# locker_unit.net
KiCad netlist of a schematic drawn in EAGLE
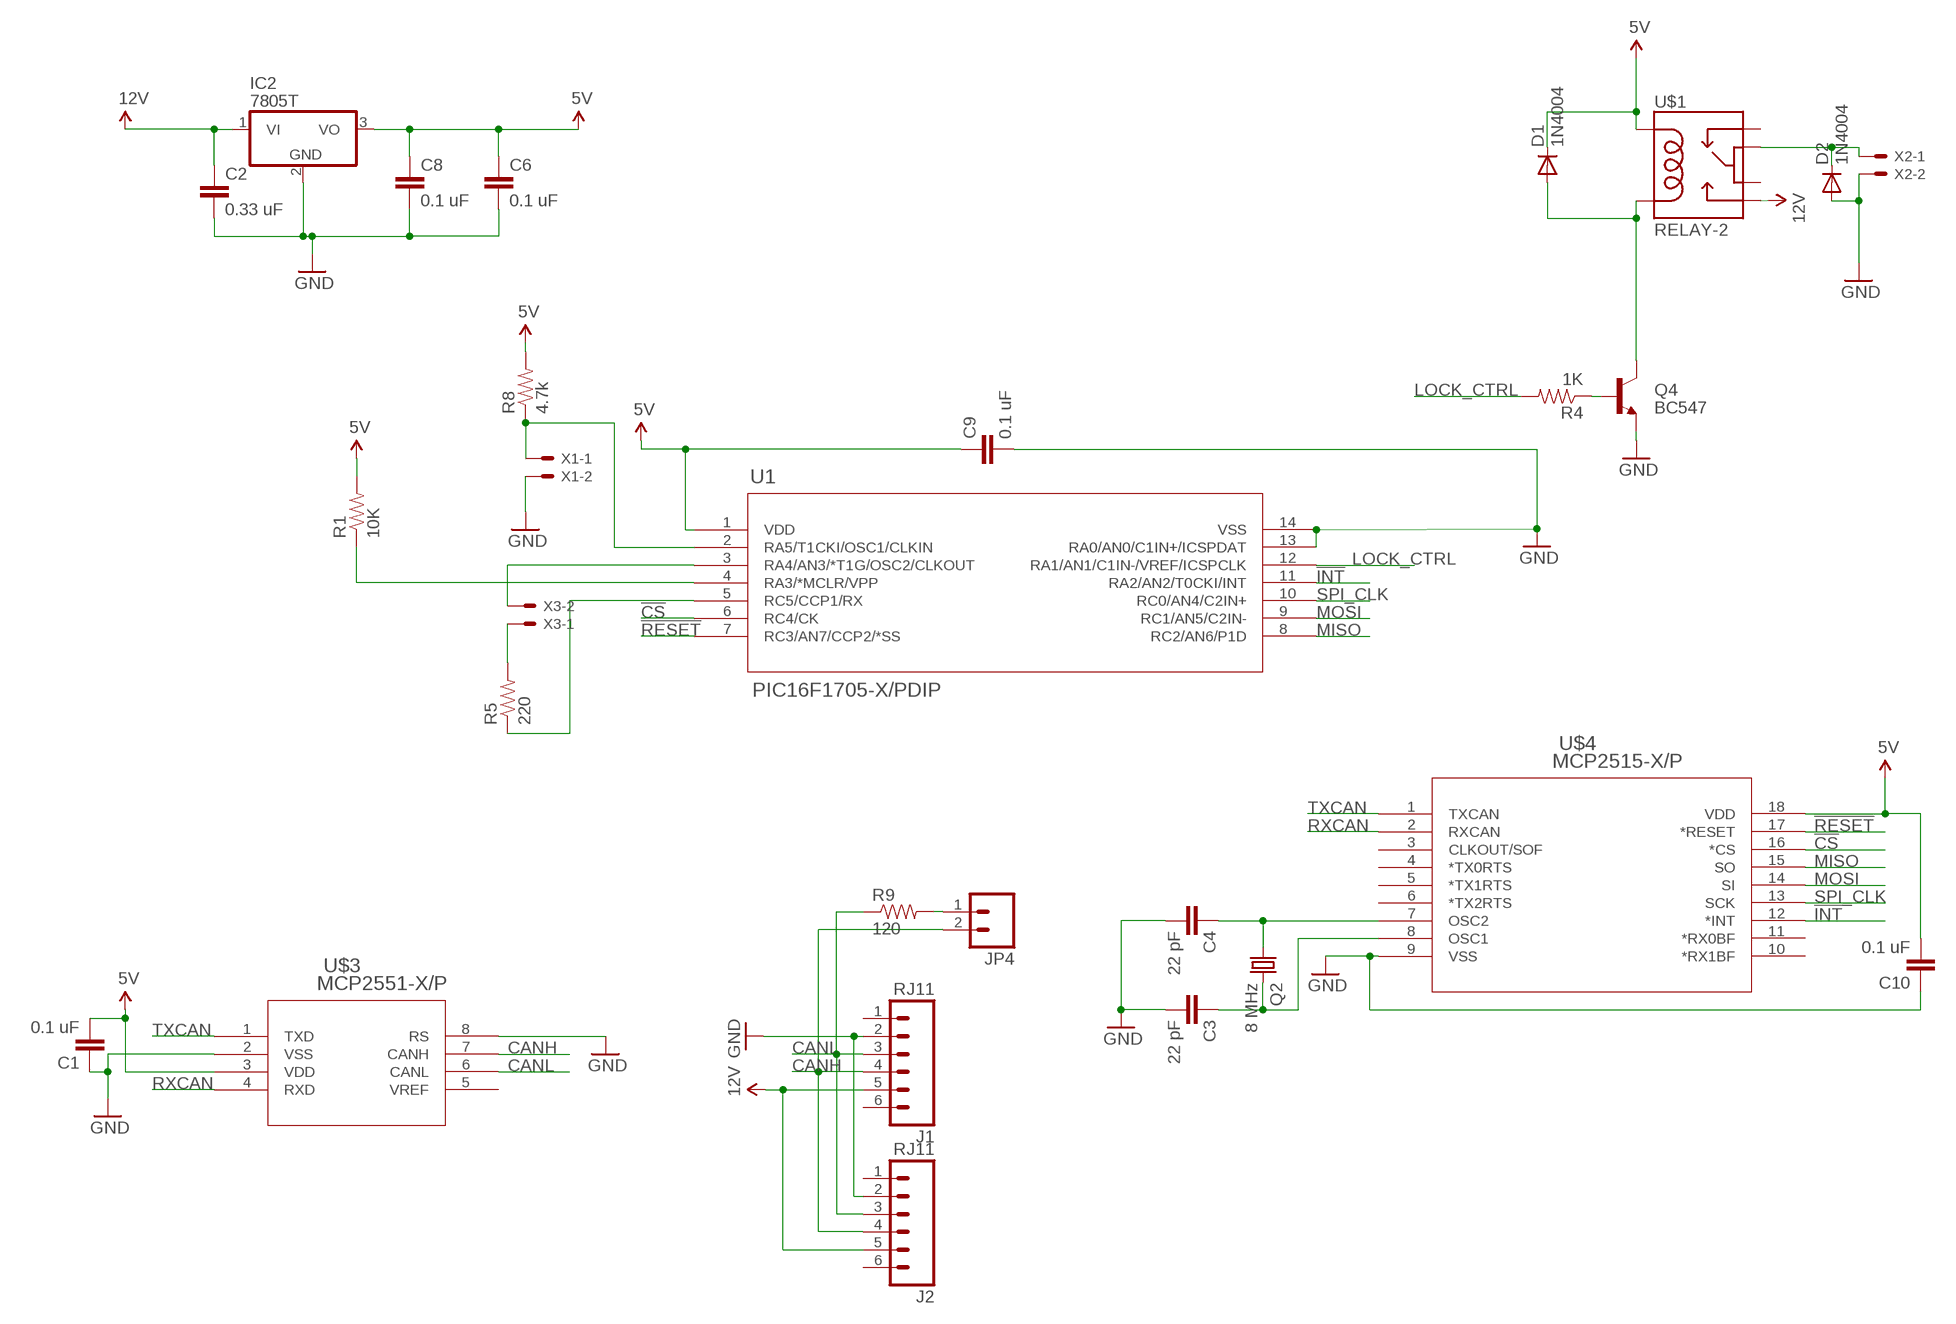
[diagram p0: schematic, sheet 1]

(export (version "E")
  (design (tool "Eeschema 10.0.6"))
  (components
    (comp (ref "C1")
      (value "0.1 uF")
      (footprint "eagle-import:C050-030X075")
      (libsource (lib "eagle-import") (part "C-EU050-030X075"))
    )
    (comp (ref "C2")
      (value "0.33 uF")
      (footprint "eagle-import:C050-030X075")
      (libsource (lib "eagle-import") (part "C-EU050-030X075"))
    )
    (comp (ref "C3")
      (value "22 pF")
      (footprint "eagle-import:C025-025X050")
      (libsource (lib "eagle-import") (part "C-EU025-025X050"))
    )
    (comp (ref "C4")
      (value "22 pF")
      (footprint "eagle-import:C025-025X050")
      (libsource (lib "eagle-import") (part "C-EU025-025X050"))
    )
    (comp (ref "C6")
      (value "0.1 uF")
      (footprint "eagle-import:C050-030X075")
      (libsource (lib "eagle-import") (part "C-EU050-030X075"))
    )
    (comp (ref "C8")
      (value "0.1 uF")
      (footprint "eagle-import:C050-030X075")
      (libsource (lib "eagle-import") (part "C-EU050-030X075"))
    )
    (comp (ref "C9")
      (value "0.1 uF")
      (footprint "eagle-import:C050-030X075")
      (libsource (lib "eagle-import") (part "C-EU050-030X075"))
    )
    (comp (ref "C10")
      (value "0.1 uF")
      (footprint "eagle-import:C050-030X075")
      (libsource (lib "eagle-import") (part "C-EU050-030X075"))
    )
    (comp (ref "D1")
      (value "1N4004")
      (footprint "eagle-import:DO41-10")
      (libsource (lib "eagle-import") (part "1N4004"))
    )
    (comp (ref "D2")
      (value "1N4004")
      (footprint "eagle-import:DO41-10")
      (libsource (lib "eagle-import") (part "1N4004"))
    )
    (comp (ref "IC2")
      (value "7805T")
      (footprint "eagle-import:TO220H")
      (libsource (lib "eagle-import") (part "78T05"))
    )
    (comp (ref "J1")
      (value "RJ11")
      (footprint "eagle-import:RJ11-6")
      (libsource (lib "eagle-import") (part "RJ11-6PTH"))
    )
    (comp (ref "J2")
      (value "RJ11")
      (footprint "eagle-import:RJ11-6")
      (libsource (lib "eagle-import") (part "RJ11-6PTH"))
    )
    (comp (ref "JP4")
      (value "M02PTH")
      (footprint "eagle-import:1X02")
      (libsource (lib "eagle-import") (part "M02PTH"))
    )
    (comp (ref "Q2")
      (value "8 MHz")
      (footprint "eagle-import:HC49US")
      (libsource (lib "eagle-import") (part "CRYSTALHC49US"))
    )
    (comp (ref "Q4")
      (value "BC547")
      (footprint "eagle-import:TO-92-AMMO")
      (libsource (lib "eagle-import") (part "TRANSISTOR_NPNBC547"))
    )
    (comp (ref "R1")
      (value "10K")
      (footprint "eagle-import:AXIAL-0.3")
      (libsource (lib "eagle-import") (part "RESISTORAXIAL-0.3"))
    )
    (comp (ref "R4")
      (value "1K")
      (footprint "eagle-import:AXIAL-0.3")
      (libsource (lib "eagle-import") (part "RESISTORAXIAL-0.3"))
    )
    (comp (ref "R5")
      (value "220")
      (footprint "eagle-import:AXIAL-0.3")
      (libsource (lib "eagle-import") (part "RESISTORAXIAL-0.3"))
    )
    (comp (ref "R8")
      (value "4.7k")
      (footprint "eagle-import:AXIAL-0.3")
      (libsource (lib "eagle-import") (part "RESISTORAXIAL-0.3"))
    )
    (comp (ref "R9")
      (value "120")
      (footprint "eagle-import:AXIAL-0.3")
      (libsource (lib "eagle-import") (part "RESISTORAXIAL-0.3"))
    )
    (comp (ref "U$1")
      (value "RELAY-2")
      (footprint "eagle-import:RELAY-SY")
      (libsource (lib "eagle-import") (part "RELAY-2"))
    )
    (comp (ref "U$3")
      (value "MCP2551-X/P")
      (footprint "eagle-import:PDIP8_300MC")
      (libsource (lib "eagle-import") (part "MCP2551-X/P"))
    )
    (comp (ref "U$4")
      (value "MCP2515-X/P")
      (footprint "eagle-import:PDIP18_300MC")
      (libsource (lib "eagle-import") (part "MCP2515-X/P"))
    )
    (comp (ref "U1")
      (value "PIC16F1705-X/PDIP")
      (footprint "eagle-import:PDIP14_300MC")
      (libsource (lib "eagle-import") (part "PIC16F1705-X/PDIP"))
    )
    (comp (ref "X1")
      (value "KK-156-2")
      (footprint "eagle-import:KK-156-2")
      (libsource (lib "eagle-import") (part "KK-156-2"))
    )
    (comp (ref "X2")
      (value "KK-156-2")
      (footprint "eagle-import:KK-156-2")
      (libsource (lib "eagle-import") (part "KK-156-2"))
    )
    (comp (ref "X3")
      (value "KK-156-2")
      (footprint "eagle-import:KK-156-2")
      (libsource (lib "eagle-import") (part "KK-156-2"))
    )
  )
  (nets
    (net (code "1") (name "/CANH") (class "Default")
      (node (ref "J1") (pin "4") (pinfunction "4_4") (pintype "passive"))
      (node (ref "J2") (pin "4") (pinfunction "4_4") (pintype "passive"))
      (node (ref "JP4") (pin "2") (pinfunction "2_2") (pintype "passive"))
      (node (ref "U$3") (pin "7") (pinfunction "CANH_7") (pintype "passive"))
    )
    (net (code "2") (name "/CANL") (class "Default")
      (node (ref "J1") (pin "3") (pinfunction "3_3") (pintype "passive"))
      (node (ref "J2") (pin "3") (pinfunction "3_3") (pintype "passive"))
      (node (ref "R9") (pin "P$1") (pinfunction "1_P$1") (pintype "passive"))
      (node (ref "U$3") (pin "6") (pinfunction "CANL_6") (pintype "passive"))
    )
    (net (code "3") (name "/LOCK_CTRL") (class "Default")
      (node (ref "R4") (pin "P$2") (pinfunction "2_P$2") (pintype "passive"))
      (node (ref "U1") (pin "12") (pinfunction "RA1/AN1/C1IN-/VREF/ICSPCLK_12") (pintype "bidirectional"))
    )
    (net (code "4") (name "/MISO") (class "Default")
      (node (ref "U$4") (pin "15") (pinfunction "SO_15") (pintype "passive"))
      (node (ref "U1") (pin "8") (pinfunction "RC2/AN6/P1D_8") (pintype "bidirectional"))
    )
    (net (code "5") (name "/MOSI") (class "Default")
      (node (ref "U$4") (pin "14") (pinfunction "SI_14") (pintype "passive"))
      (node (ref "U1") (pin "9") (pinfunction "RC1/AN5/C2IN-_9") (pintype "bidirectional"))
    )
    (net (code "6") (name "/RXCAN") (class "Default")
      (node (ref "U$3") (pin "4") (pinfunction "RXD_4") (pintype "passive"))
      (node (ref "U$4") (pin "2") (pinfunction "RXCAN_2") (pintype "passive"))
    )
    (net (code "7") (name "/SPI_CLK") (class "Default")
      (node (ref "U$4") (pin "13") (pinfunction "SCK_13") (pintype "passive"))
      (node (ref "U1") (pin "10") (pinfunction "RC0/AN4/C2IN+_10") (pintype "bidirectional"))
    )
    (net (code "8") (name "/TXCAN") (class "Default")
      (node (ref "U$3") (pin "1") (pinfunction "TXD_1") (pintype "passive"))
      (node (ref "U$4") (pin "1") (pinfunction "TXCAN_1") (pintype "passive"))
    )
    (net (code "9") (name "/~{CS}") (class "Default")
      (node (ref "U$4") (pin "16") (pinfunction "*CS_16") (pintype "passive"))
      (node (ref "U1") (pin "6") (pinfunction "RC4/CK_6") (pintype "bidirectional"))
    )
    (net (code "10") (name "/~{INT}") (class "Default")
      (node (ref "U$4") (pin "12") (pinfunction "*INT_12") (pintype "passive"))
      (node (ref "U1") (pin "11") (pinfunction "RA2/AN2/T0CKI/INT_11") (pintype "bidirectional"))
    )
    (net (code "11") (name "/~{RESET}") (class "Default")
      (node (ref "U$4") (pin "17") (pinfunction "*RESET_17") (pintype "passive"))
      (node (ref "U1") (pin "7") (pinfunction "RC3/AN7/CCP2/*SS_7") (pintype "bidirectional"))
    )
    (net (code "12") (name "5V") (class "Default")
      (node (ref "C1") (pin "2") (pinfunction "2_2") (pintype "passive"))
      (node (ref "C10") (pin "2") (pinfunction "2_2") (pintype "passive"))
      (node (ref "C6") (pin "1") (pinfunction "1_1") (pintype "passive"))
      (node (ref "C8") (pin "1") (pinfunction "1_1") (pintype "passive"))
      (node (ref "C9") (pin "1") (pinfunction "1_1") (pintype "passive"))
      (node (ref "D1") (pin "C") (pinfunction "C_C") (pintype "passive"))
      (node (ref "IC2") (pin "3") (pinfunction "VO_3") (pintype "passive"))
      (node (ref "R1") (pin "P$2") (pinfunction "2_P$2") (pintype "passive"))
      (node (ref "R8") (pin "P$2") (pinfunction "2_P$2") (pintype "passive"))
      (node (ref "U$1") (pin "2") (pinfunction "2_2") (pintype "bidirectional"))
      (node (ref "U$3") (pin "3") (pinfunction "VDD_3") (pintype "passive"))
      (node (ref "U$4") (pin "18") (pinfunction "VDD_18") (pintype "passive"))
      (node (ref "U1") (pin "1") (pinfunction "VDD_1") (pintype "power_in"))
    )
    (net (code "13") (name "12V") (class "Default")
      (node (ref "C2") (pin "1") (pinfunction "1_1") (pintype "passive"))
      (node (ref "IC2") (pin "1") (pinfunction "VI_1") (pintype "input"))
      (node (ref "J1") (pin "5") (pinfunction "5_5") (pintype "passive"))
      (node (ref "J2") (pin "5") (pinfunction "5_5") (pintype "passive"))
      (node (ref "U$1") (pin "10") (pinfunction "10_10") (pintype "bidirectional"))
    )
    (net (code "14") (name "GND") (class "Default")
      (node (ref "C1") (pin "1") (pinfunction "1_1") (pintype "passive"))
      (node (ref "C10") (pin "1") (pinfunction "1_1") (pintype "passive"))
      (node (ref "C2") (pin "2") (pinfunction "2_2") (pintype "passive"))
      (node (ref "C3") (pin "2") (pinfunction "2_2") (pintype "passive"))
      (node (ref "C4") (pin "2") (pinfunction "2_2") (pintype "passive"))
      (node (ref "C6") (pin "2") (pinfunction "2_2") (pintype "passive"))
      (node (ref "C8") (pin "2") (pinfunction "2_2") (pintype "passive"))
      (node (ref "C9") (pin "2") (pinfunction "2_2") (pintype "passive"))
      (node (ref "D2") (pin "A") (pinfunction "A_A") (pintype "passive"))
      (node (ref "IC2") (pin "2") (pinfunction "GND_2") (pintype "passive"))
      (node (ref "J1") (pin "2") (pinfunction "2_2") (pintype "passive"))
      (node (ref "J2") (pin "2") (pinfunction "2_2") (pintype "passive"))
      (node (ref "Q4") (pin "3") (pinfunction "E_3") (pintype "passive"))
      (node (ref "U$3") (pin "2") (pinfunction "VSS_2") (pintype "passive"))
      (node (ref "U$3") (pin "8") (pinfunction "RS_8") (pintype "passive"))
      (node (ref "U$4") (pin "9") (pinfunction "VSS_9") (pintype "passive"))
      (node (ref "U1") (pin "13") (pinfunction "RA0/AN0/C1IN+/ICSPDAT_13") (pintype "bidirectional"))
      (node (ref "U1") (pin "14") (pinfunction "VSS_14") (pintype "power_in"))
      (node (ref "X1") (pin "2") (pinfunction "S_2") (pintype "passive"))
      (node (ref "X2") (pin "2") (pinfunction "S_2") (pintype "passive"))
    )
    (net (code "15") (name "Net-(Q4-B)") (class "Default")
      (node (ref "Q4") (pin "2") (pinfunction "B_2") (pintype "passive"))
      (node (ref "R4") (pin "P$1") (pinfunction "1_P$1") (pintype "passive"))
    )
    (net (code "16") (name "Net-(Q4-C)") (class "Default")
      (node (ref "D1") (pin "A") (pinfunction "A_A") (pintype "passive"))
      (node (ref "Q4") (pin "1") (pinfunction "C_1") (pintype "passive"))
      (node (ref "U$1") (pin "9") (pinfunction "9_9") (pintype "bidirectional"))
    )
    (net (code "17") (name "Net-(R1-1)") (class "Default")
      (node (ref "R1") (pin "P$1") (pinfunction "1_P$1") (pintype "passive"))
      (node (ref "U1") (pin "4") (pinfunction "RA3/*MCLR/VPP_4") (pintype "bidirectional"))
    )
    (net (code "18") (name "Net-(R5-1)") (class "Default")
      (node (ref "R5") (pin "P$1") (pinfunction "1_P$1") (pintype "passive"))
      (node (ref "U1") (pin "5") (pinfunction "RC5/CCP1/RX_5") (pintype "bidirectional"))
    )
    (net (code "19") (name "Net-(R5-2)") (class "Default")
      (node (ref "R5") (pin "P$2") (pinfunction "2_P$2") (pintype "passive"))
      (node (ref "X3") (pin "1") (pinfunction "S_1") (pintype "passive"))
    )
    (net (code "20") (name "Net-(R8-1)") (class "Default")
      (node (ref "R8") (pin "P$1") (pinfunction "1_P$1") (pintype "passive"))
      (node (ref "U1") (pin "2") (pinfunction "RA5/T1CKI/OSC1/CLKIN_2") (pintype "bidirectional"))
      (node (ref "X1") (pin "1") (pinfunction "S_1") (pintype "passive"))
    )
    (net (code "21") (name "Net-(R9-2)") (class "Default")
      (node (ref "JP4") (pin "1") (pinfunction "1_1") (pintype "passive"))
      (node (ref "R9") (pin "P$2") (pinfunction "2_P$2") (pintype "passive"))
    )
    (net (code "22") (name "Net-(U$4-OSC1)") (class "Default")
      (node (ref "C3") (pin "1") (pinfunction "1_1") (pintype "passive"))
      (node (ref "Q2") (pin "2") (pinfunction "2_2") (pintype "passive"))
      (node (ref "U$4") (pin "8") (pinfunction "OSC1_8") (pintype "passive"))
    )
    (net (code "23") (name "Net-(U$4-OSC2)") (class "Default")
      (node (ref "C4") (pin "1") (pinfunction "1_1") (pintype "passive"))
      (node (ref "Q2") (pin "1") (pinfunction "1_1") (pintype "passive"))
      (node (ref "U$4") (pin "7") (pinfunction "OSC2_7") (pintype "passive"))
    )
    (net (code "24") (name "Net-(U1-RA4{slash}AN3{slash}*T1G{slash}OSC2{slash}CLKOUT)") (class "Default")
      (node (ref "U1") (pin "3") (pinfunction "RA4/AN3/*T1G/OSC2/CLKOUT_3") (pintype "bidirectional"))
      (node (ref "X3") (pin "2") (pinfunction "S_2") (pintype "passive"))
    )
    (net (code "25") (name "Net-(X2A-S)") (class "Default")
      (node (ref "D2") (pin "C") (pinfunction "C_C") (pintype "passive"))
      (node (ref "U$1") (pin "5") (pinfunction "5_5") (pintype "bidirectional"))
      (node (ref "X2") (pin "1") (pinfunction "S_1") (pintype "passive"))
    )
    (net (code "26") (name "unconnected-(J1-Pad1)") (class "Default")
      (node (ref "J1") (pin "1") (pinfunction "1_1") (pintype "passive"))
    )
    (net (code "27") (name "unconnected-(J1-Pad6)") (class "Default")
      (node (ref "J1") (pin "6") (pinfunction "6_6") (pintype "passive"))
    )
    (net (code "28") (name "unconnected-(J2-Pad1)") (class "Default")
      (node (ref "J2") (pin "1") (pinfunction "1_1") (pintype "passive"))
    )
    (net (code "29") (name "unconnected-(J2-Pad6)") (class "Default")
      (node (ref "J2") (pin "6") (pinfunction "6_6") (pintype "passive"))
    )
    (net (code "30") (name "unconnected-(U$1-Pad1)") (class "Default")
      (node (ref "U$1") (pin "1") (pinfunction "1_1") (pintype "bidirectional"))
    )
    (net (code "31") (name "unconnected-(U$1-Pad6)") (class "Default")
      (node (ref "U$1") (pin "6") (pinfunction "6_6") (pintype "bidirectional"))
    )
    (net (code "32") (name "unconnected-(U$3-VREF-Pad5)") (class "Default")
      (node (ref "U$3") (pin "5") (pinfunction "VREF_5") (pintype "passive"))
    )
    (net (code "33") (name "unconnected-(U$4-*RX0BF-Pad11)") (class "Default")
      (node (ref "U$4") (pin "11") (pinfunction "*RX0BF_11") (pintype "passive"))
    )
    (net (code "34") (name "unconnected-(U$4-*RX1BF-Pad10)") (class "Default")
      (node (ref "U$4") (pin "10") (pinfunction "*RX1BF_10") (pintype "passive"))
    )
    (net (code "35") (name "unconnected-(U$4-*TX0RTS-Pad4)") (class "Default")
      (node (ref "U$4") (pin "4") (pinfunction "*TX0RTS_4") (pintype "passive"))
    )
    (net (code "36") (name "unconnected-(U$4-*TX1RTS-Pad5)") (class "Default")
      (node (ref "U$4") (pin "5") (pinfunction "*TX1RTS_5") (pintype "passive"))
    )
    (net (code "37") (name "unconnected-(U$4-*TX2RTS-Pad6)") (class "Default")
      (node (ref "U$4") (pin "6") (pinfunction "*TX2RTS_6") (pintype "passive"))
    )
    (net (code "38") (name "unconnected-(U$4-CLKOUT{slash}SOF-Pad3)") (class "Default")
      (node (ref "U$4") (pin "3") (pinfunction "CLKOUT/SOF_3") (pintype "passive"))
    )
  )
)
